# Extension_Connectors.net
KiCad netlist of a schematic drawn in Altium Designer
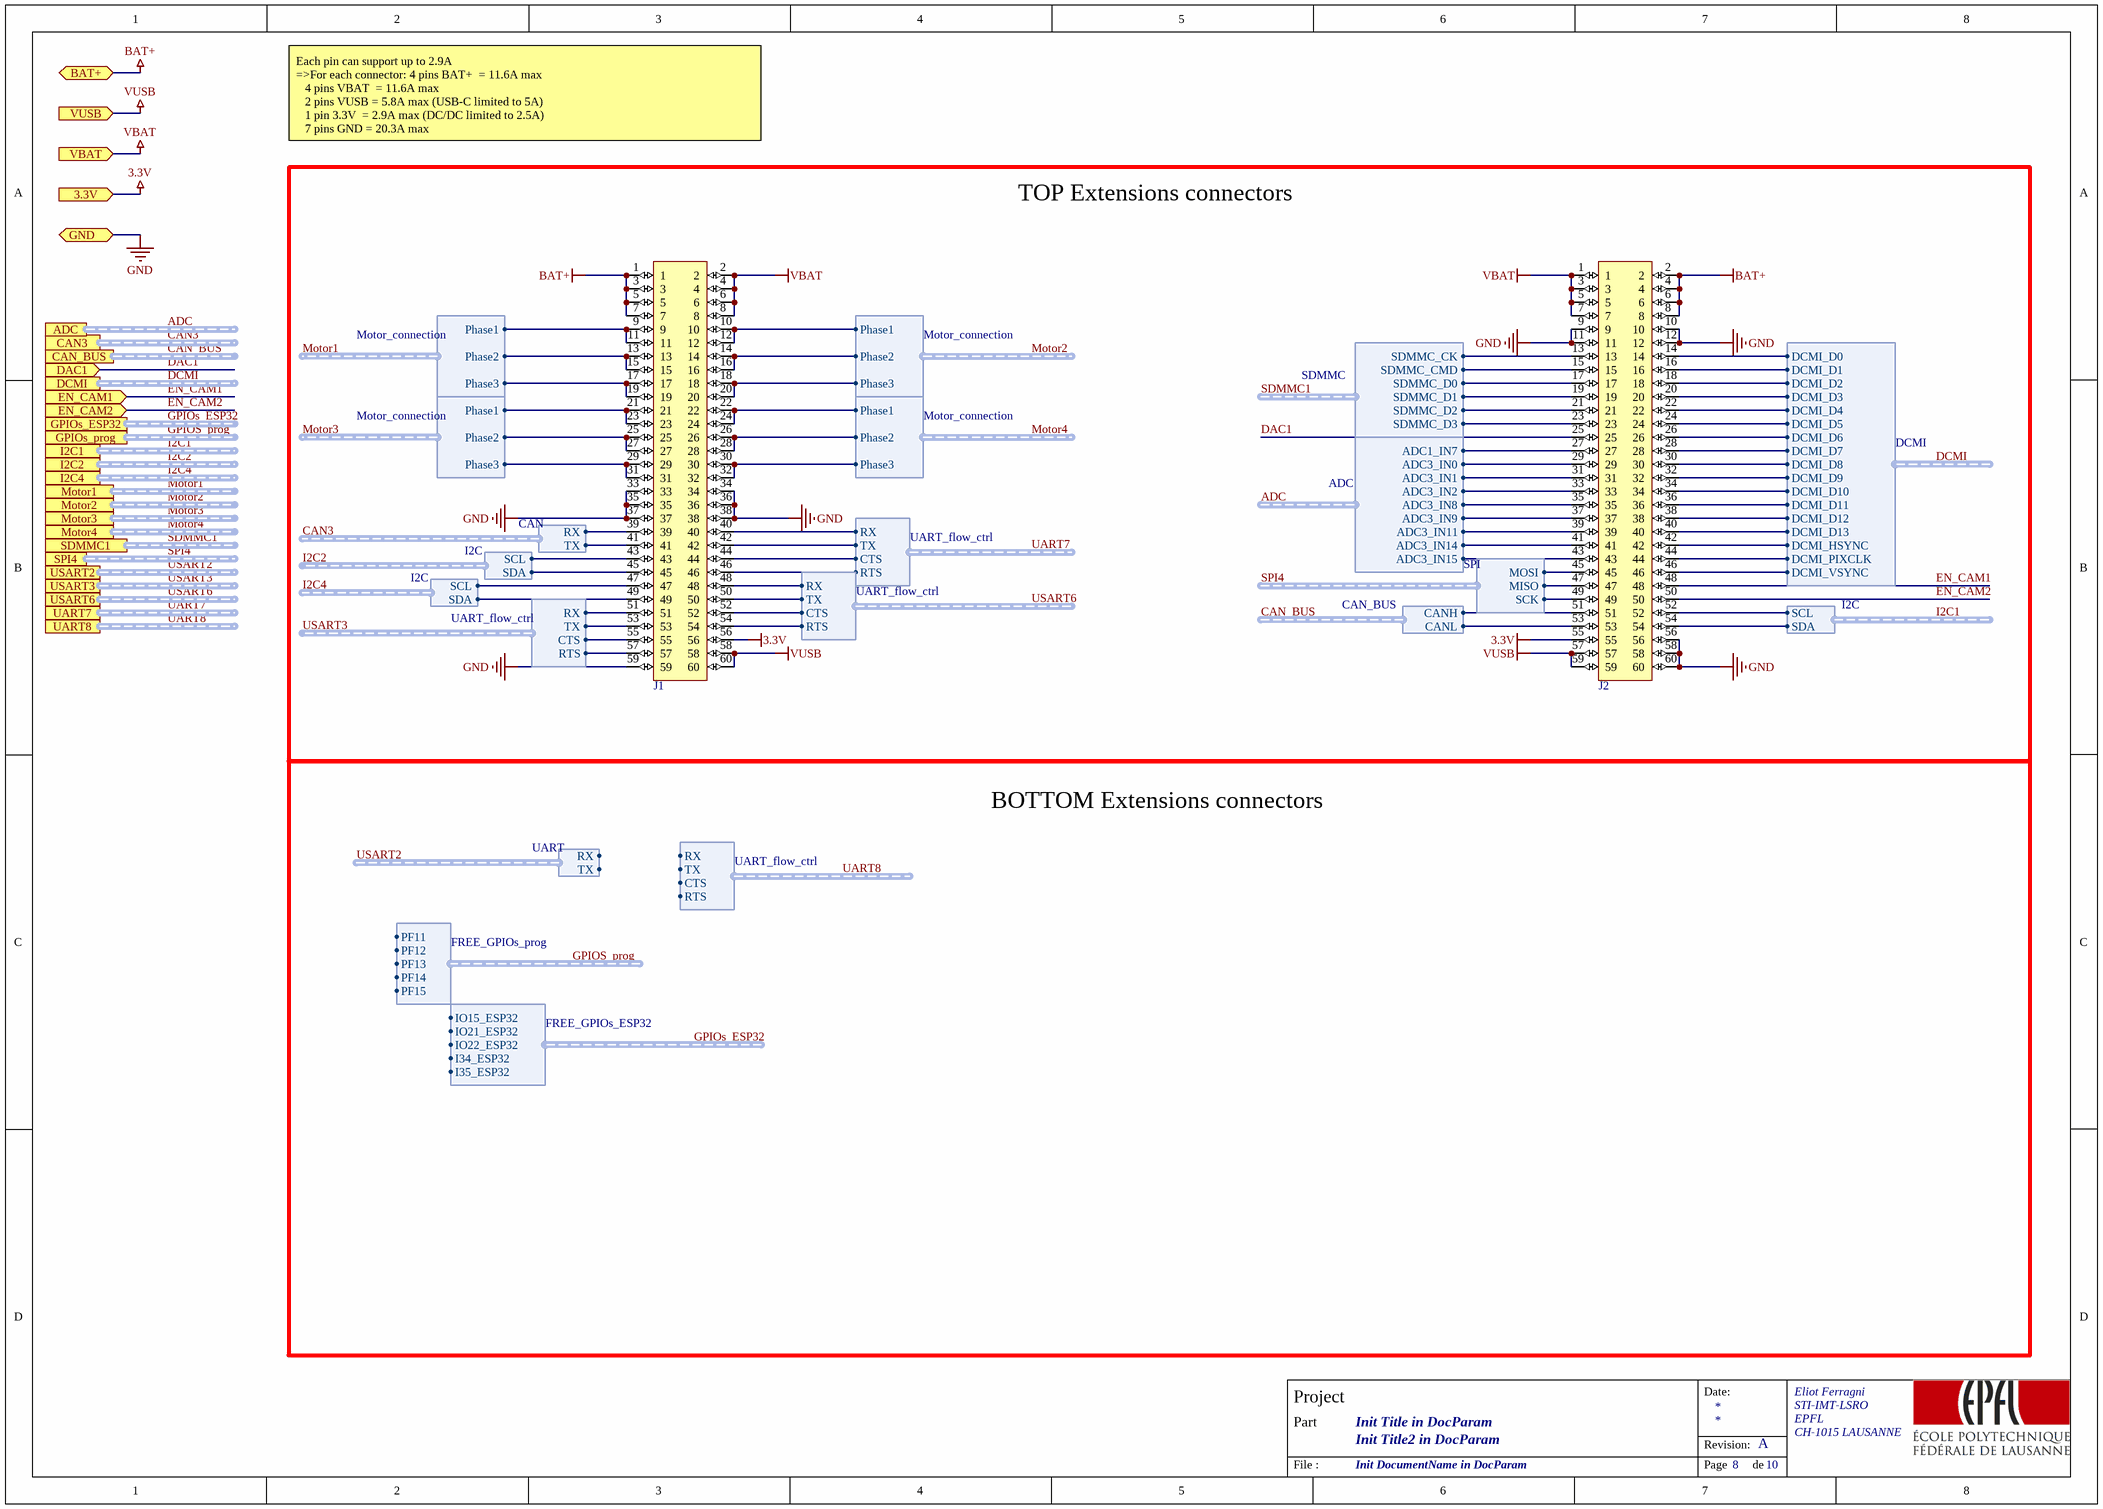
[diagram p0: Extension_Connectors.SchDoc]

(export (version "E")
  (design (tool "Eeschema 10.0.6"))
  (components
    (comp (ref "J1")
      (value "FLE-130-01-G-DV-A")
      (footprint "FLE-130-01-G-DV-A")
      (description ".050 MICRO STRIPS")
      (fields (field (name "MANUFACTURER") "Samtec Inc."))
      (libsource (lib "Schlib") (part "FLE-130-01-G-DV-A"))
    )
    (comp (ref "J2")
      (value "FLE-130-01-G-DV-A")
      (footprint "FLE-130-01-G-DV-A")
      (description ".050 MICRO STRIPS")
      (fields (field (name "MANUFACTURER") "Samtec Inc."))
      (libsource (lib "Schlib") (part "FLE-130-01-G-DV-A"))
    )
  )
  (nets
    (net (code "41") (name "/ADC1_IN7") (class "Default")
      (node (ref "J2") (pin "27") (pinfunction "27_27") (pintype "bidirectional"))
    )
    (net (code "42") (name "/ADC3_IN0") (class "Default")
      (node (ref "J2") (pin "29") (pinfunction "29_29") (pintype "bidirectional"))
    )
    (net (code "43") (name "/ADC3_IN1") (class "Default")
      (node (ref "J2") (pin "31") (pinfunction "31_31") (pintype "bidirectional"))
    )
    (net (code "44") (name "/ADC3_IN2") (class "Default")
      (node (ref "J2") (pin "33") (pinfunction "33_33") (pintype "bidirectional"))
    )
    (net (code "45") (name "/ADC3_IN8") (class "Default")
      (node (ref "J2") (pin "35") (pinfunction "35_35") (pintype "bidirectional"))
    )
    (net (code "46") (name "/ADC3_IN9") (class "Default")
      (node (ref "J2") (pin "37") (pinfunction "37_37") (pintype "bidirectional"))
    )
    (net (code "47") (name "/ADC3_IN11") (class "Default")
      (node (ref "J2") (pin "39") (pinfunction "39_39") (pintype "bidirectional"))
    )
    (net (code "48") (name "/ADC3_IN14") (class "Default")
      (node (ref "J2") (pin "41") (pinfunction "41_41") (pintype "bidirectional"))
    )
    (net (code "49") (name "/ADC3_IN15") (class "Default")
      (node (ref "J2") (pin "43") (pinfunction "43_43") (pintype "bidirectional"))
    )
    (net (code "52") (name "/CANH") (class "Default")
      (node (ref "J2") (pin "51") (pinfunction "51_51") (pintype "bidirectional"))
    )
    (net (code "53") (name "/CANL") (class "Default")
      (node (ref "J2") (pin "53") (pinfunction "53_53") (pintype "bidirectional"))
    )
    (net (code "55") (name "/DAC1") (class "Default")
      (node (ref "J2") (pin "25") (pinfunction "25_25") (pintype "bidirectional"))
    )
    (net (code "56") (name "/DCMI_D0") (class "Default")
      (node (ref "J2") (pin "14") (pinfunction "14_14") (pintype "bidirectional"))
    )
    (net (code "57") (name "/DCMI_D1") (class "Default")
      (node (ref "J2") (pin "16") (pinfunction "16_16") (pintype "bidirectional"))
    )
    (net (code "58") (name "/DCMI_D2") (class "Default")
      (node (ref "J2") (pin "18") (pinfunction "18_18") (pintype "bidirectional"))
    )
    (net (code "59") (name "/DCMI_D3") (class "Default")
      (node (ref "J2") (pin "20") (pinfunction "20_20") (pintype "bidirectional"))
    )
    (net (code "60") (name "/DCMI_D4") (class "Default")
      (node (ref "J2") (pin "22") (pinfunction "22_22") (pintype "bidirectional"))
    )
    (net (code "61") (name "/DCMI_D5") (class "Default")
      (node (ref "J2") (pin "24") (pinfunction "24_24") (pintype "bidirectional"))
    )
    (net (code "62") (name "/DCMI_D6") (class "Default")
      (node (ref "J2") (pin "26") (pinfunction "26_26") (pintype "bidirectional"))
    )
    (net (code "63") (name "/DCMI_D7") (class "Default")
      (node (ref "J2") (pin "28") (pinfunction "28_28") (pintype "bidirectional"))
    )
    (net (code "64") (name "/DCMI_D8") (class "Default")
      (node (ref "J2") (pin "30") (pinfunction "30_30") (pintype "bidirectional"))
    )
    (net (code "65") (name "/DCMI_D9") (class "Default")
      (node (ref "J2") (pin "32") (pinfunction "32_32") (pintype "bidirectional"))
    )
    (net (code "66") (name "/DCMI_D10") (class "Default")
      (node (ref "J2") (pin "34") (pinfunction "34_34") (pintype "bidirectional"))
    )
    (net (code "67") (name "/DCMI_D11") (class "Default")
      (node (ref "J2") (pin "36") (pinfunction "36_36") (pintype "bidirectional"))
    )
    (net (code "68") (name "/DCMI_D12") (class "Default")
      (node (ref "J2") (pin "38") (pinfunction "38_38") (pintype "bidirectional"))
    )
    (net (code "69") (name "/DCMI_D13") (class "Default")
      (node (ref "J2") (pin "40") (pinfunction "40_40") (pintype "bidirectional"))
    )
    (net (code "70") (name "/DCMI_HSYNC") (class "Default")
      (node (ref "J2") (pin "42") (pinfunction "42_42") (pintype "bidirectional"))
    )
    (net (code "71") (name "/DCMI_PIXCLK") (class "Default")
      (node (ref "J2") (pin "44") (pinfunction "44_44") (pintype "bidirectional"))
    )
    (net (code "72") (name "/DCMI_VSYNC") (class "Default")
      (node (ref "J2") (pin "46") (pinfunction "46_46") (pintype "bidirectional"))
    )
    (net (code "74") (name "/EN_CAM1") (class "Default")
      (node (ref "J2") (pin "48") (pinfunction "48_48") (pintype "bidirectional"))
    )
    (net (code "75") (name "/EN_CAM2") (class "Default")
      (node (ref "J2") (pin "50") (pinfunction "50_50") (pintype "bidirectional"))
    )
    (net (code "81") (name "/MISO") (class "Default")
      (node (ref "J2") (pin "47") (pinfunction "47_47") (pintype "bidirectional"))
    )
    (net (code "82") (name "/MOSI") (class "Default")
      (node (ref "J2") (pin "45") (pinfunction "45_45") (pintype "bidirectional"))
    )
    (net (code "87") (name "/SCK") (class "Default")
      (node (ref "J2") (pin "49") (pinfunction "49_49") (pintype "bidirectional"))
    )
    (net (code "89") (name "/SDMMC_CK") (class "Default")
      (node (ref "J2") (pin "13") (pinfunction "13_13") (pintype "bidirectional"))
    )
    (net (code "90") (name "/SDMMC_CMD") (class "Default")
      (node (ref "J2") (pin "15") (pinfunction "15_15") (pintype "bidirectional"))
    )
    (net (code "91") (name "/SDMMC_D0") (class "Default")
      (node (ref "J2") (pin "17") (pinfunction "17_17") (pintype "bidirectional"))
    )
    (net (code "92") (name "/SDMMC_D1") (class "Default")
      (node (ref "J2") (pin "19") (pinfunction "19_19") (pintype "bidirectional"))
    )
    (net (code "93") (name "/SDMMC_D2") (class "Default")
      (node (ref "J2") (pin "21") (pinfunction "21_21") (pintype "bidirectional"))
    )
    (net (code "94") (name "/SDMMC_D3") (class "Default")
      (node (ref "J2") (pin "23") (pinfunction "23_23") (pintype "bidirectional"))
    )
    (net (code "102") (name "3.3V") (class "Default")
      (node (ref "J1") (pin "56") (pinfunction "56_56") (pintype "bidirectional"))
      (node (ref "J2") (pin "55") (pinfunction "55_55") (pintype "bidirectional"))
    )
    (net (code "103") (name "BAT+") (class "Default")
      (node (ref "J1") (pin "1") (pinfunction "1_1") (pintype "bidirectional"))
      (node (ref "J1") (pin "3") (pinfunction "3_3") (pintype "bidirectional"))
      (node (ref "J1") (pin "5") (pinfunction "5_5") (pintype "bidirectional"))
      (node (ref "J1") (pin "7") (pinfunction "7_7") (pintype "bidirectional"))
      (node (ref "J2") (pin "2") (pinfunction "2_2") (pintype "bidirectional"))
      (node (ref "J2") (pin "4") (pinfunction "4_4") (pintype "bidirectional"))
      (node (ref "J2") (pin "6") (pinfunction "6_6") (pintype "bidirectional"))
      (node (ref "J2") (pin "8") (pinfunction "8_8") (pintype "bidirectional"))
    )
    (net (code "104") (name "GND") (class "Default")
      (node (ref "J1") (pin "33") (pinfunction "33_33") (pintype "bidirectional"))
      (node (ref "J1") (pin "34") (pinfunction "34_34") (pintype "bidirectional"))
      (node (ref "J1") (pin "35") (pinfunction "35_35") (pintype "bidirectional"))
      (node (ref "J1") (pin "36") (pinfunction "36_36") (pintype "bidirectional"))
      (node (ref "J1") (pin "37") (pinfunction "37_37") (pintype "bidirectional"))
      (node (ref "J1") (pin "38") (pinfunction "38_38") (pintype "bidirectional"))
      (node (ref "J1") (pin "59") (pinfunction "59_59") (pintype "bidirectional"))
      (node (ref "J2") (pin "10") (pinfunction "10_10") (pintype "bidirectional"))
      (node (ref "J2") (pin "11") (pinfunction "11_11") (pintype "bidirectional"))
      (node (ref "J2") (pin "12") (pinfunction "12_12") (pintype "bidirectional"))
      (node (ref "J2") (pin "56") (pinfunction "56_56") (pintype "bidirectional"))
      (node (ref "J2") (pin "58") (pinfunction "58_58") (pintype "bidirectional"))
      (node (ref "J2") (pin "60") (pinfunction "60_60") (pintype "bidirectional"))
      (node (ref "J2") (pin "9") (pinfunction "9_9") (pintype "bidirectional"))
    )
    (net (code "105") (name "Net-(J1-Pad10)") (class "Default")
      (node (ref "J1") (pin "10") (pinfunction "10_10") (pintype "bidirectional"))
      (node (ref "J1") (pin "12") (pinfunction "12_12") (pintype "bidirectional"))
    )
    (net (code "106") (name "Net-(J1-Pad11)") (class "Default")
      (node (ref "J1") (pin "11") (pinfunction "11_11") (pintype "bidirectional"))
      (node (ref "J1") (pin "9") (pinfunction "9_9") (pintype "bidirectional"))
    )
    (net (code "107") (name "Net-(J1-Pad13)") (class "Default")
      (node (ref "J1") (pin "13") (pinfunction "13_13") (pintype "bidirectional"))
      (node (ref "J1") (pin "15") (pinfunction "15_15") (pintype "bidirectional"))
    )
    (net (code "108") (name "Net-(J1-Pad14)") (class "Default")
      (node (ref "J1") (pin "14") (pinfunction "14_14") (pintype "bidirectional"))
      (node (ref "J1") (pin "16") (pinfunction "16_16") (pintype "bidirectional"))
    )
    (net (code "109") (name "Net-(J1-Pad17)") (class "Default")
      (node (ref "J1") (pin "17") (pinfunction "17_17") (pintype "bidirectional"))
      (node (ref "J1") (pin "19") (pinfunction "19_19") (pintype "bidirectional"))
    )
    (net (code "110") (name "Net-(J1-Pad18)") (class "Default")
      (node (ref "J1") (pin "18") (pinfunction "18_18") (pintype "bidirectional"))
      (node (ref "J1") (pin "20") (pinfunction "20_20") (pintype "bidirectional"))
    )
    (net (code "111") (name "Net-(J1-Pad21)") (class "Default")
      (node (ref "J1") (pin "21") (pinfunction "21_21") (pintype "bidirectional"))
      (node (ref "J1") (pin "23") (pinfunction "23_23") (pintype "bidirectional"))
    )
    (net (code "112") (name "Net-(J1-Pad22)") (class "Default")
      (node (ref "J1") (pin "22") (pinfunction "22_22") (pintype "bidirectional"))
      (node (ref "J1") (pin "24") (pinfunction "24_24") (pintype "bidirectional"))
    )
    (net (code "113") (name "Net-(J1-Pad25)") (class "Default")
      (node (ref "J1") (pin "25") (pinfunction "25_25") (pintype "bidirectional"))
      (node (ref "J1") (pin "27") (pinfunction "27_27") (pintype "bidirectional"))
    )
    (net (code "114") (name "Net-(J1-Pad26)") (class "Default")
      (node (ref "J1") (pin "26") (pinfunction "26_26") (pintype "bidirectional"))
      (node (ref "J1") (pin "28") (pinfunction "28_28") (pintype "bidirectional"))
    )
    (net (code "115") (name "Net-(J1-Pad29)") (class "Default")
      (node (ref "J1") (pin "29") (pinfunction "29_29") (pintype "bidirectional"))
      (node (ref "J1") (pin "31") (pinfunction "31_31") (pintype "bidirectional"))
    )
    (net (code "116") (name "Net-(J1-Pad30)") (class "Default")
      (node (ref "J1") (pin "30") (pinfunction "30_30") (pintype "bidirectional"))
      (node (ref "J1") (pin "32") (pinfunction "32_32") (pintype "bidirectional"))
    )
    (net (code "117") (name "VBAT") (class "Default")
      (node (ref "J1") (pin "2") (pinfunction "2_2") (pintype "bidirectional"))
      (node (ref "J1") (pin "4") (pinfunction "4_4") (pintype "bidirectional"))
      (node (ref "J1") (pin "6") (pinfunction "6_6") (pintype "bidirectional"))
      (node (ref "J1") (pin "8") (pinfunction "8_8") (pintype "bidirectional"))
      (node (ref "J2") (pin "1") (pinfunction "1_1") (pintype "bidirectional"))
      (node (ref "J2") (pin "3") (pinfunction "3_3") (pintype "bidirectional"))
      (node (ref "J2") (pin "5") (pinfunction "5_5") (pintype "bidirectional"))
      (node (ref "J2") (pin "7") (pinfunction "7_7") (pintype "bidirectional"))
    )
    (net (code "118") (name "VUSB") (class "Default")
      (node (ref "J1") (pin "58") (pinfunction "58_58") (pintype "bidirectional"))
      (node (ref "J1") (pin "60") (pinfunction "60_60") (pintype "bidirectional"))
      (node (ref "J2") (pin "57") (pinfunction "57_57") (pintype "bidirectional"))
      (node (ref "J2") (pin "59") (pinfunction "59_59") (pintype "bidirectional"))
    )
    (net (code "119") (name "unconnected-(J1-Pad39)") (class "Default")
      (node (ref "J1") (pin "39") (pinfunction "39_39") (pintype "bidirectional"))
    )
    (net (code "120") (name "unconnected-(J1-Pad40)") (class "Default")
      (node (ref "J1") (pin "40") (pinfunction "40_40") (pintype "bidirectional"))
    )
    (net (code "121") (name "unconnected-(J1-Pad41)") (class "Default")
      (node (ref "J1") (pin "41") (pinfunction "41_41") (pintype "bidirectional"))
    )
    (net (code "122") (name "unconnected-(J1-Pad42)") (class "Default")
      (node (ref "J1") (pin "42") (pinfunction "42_42") (pintype "bidirectional"))
    )
    (net (code "123") (name "unconnected-(J1-Pad43)") (class "Default")
      (node (ref "J1") (pin "43") (pinfunction "43_43") (pintype "bidirectional"))
    )
    (net (code "124") (name "unconnected-(J1-Pad44)") (class "Default")
      (node (ref "J1") (pin "44") (pinfunction "44_44") (pintype "bidirectional"))
    )
    (net (code "125") (name "unconnected-(J1-Pad45)") (class "Default")
      (node (ref "J1") (pin "45") (pinfunction "45_45") (pintype "bidirectional"))
    )
    (net (code "126") (name "unconnected-(J1-Pad46)") (class "Default")
      (node (ref "J1") (pin "46") (pinfunction "46_46") (pintype "bidirectional"))
    )
    (net (code "127") (name "unconnected-(J1-Pad47)") (class "Default")
      (node (ref "J1") (pin "47") (pinfunction "47_47") (pintype "bidirectional"))
    )
    (net (code "128") (name "unconnected-(J1-Pad48)") (class "Default")
      (node (ref "J1") (pin "48") (pinfunction "48_48") (pintype "bidirectional"))
    )
    (net (code "129") (name "unconnected-(J1-Pad49)") (class "Default")
      (node (ref "J1") (pin "49") (pinfunction "49_49") (pintype "bidirectional"))
    )
    (net (code "130") (name "unconnected-(J1-Pad50)") (class "Default")
      (node (ref "J1") (pin "50") (pinfunction "50_50") (pintype "bidirectional"))
    )
    (net (code "131") (name "unconnected-(J1-Pad51)") (class "Default")
      (node (ref "J1") (pin "51") (pinfunction "51_51") (pintype "bidirectional"))
    )
    (net (code "132") (name "unconnected-(J1-Pad52)") (class "Default")
      (node (ref "J1") (pin "52") (pinfunction "52_52") (pintype "bidirectional"))
    )
    (net (code "133") (name "unconnected-(J1-Pad53)") (class "Default")
      (node (ref "J1") (pin "53") (pinfunction "53_53") (pintype "bidirectional"))
    )
    (net (code "134") (name "unconnected-(J1-Pad54)") (class "Default")
      (node (ref "J1") (pin "54") (pinfunction "54_54") (pintype "bidirectional"))
    )
    (net (code "135") (name "unconnected-(J1-Pad55)") (class "Default")
      (node (ref "J1") (pin "55") (pinfunction "55_55") (pintype "bidirectional"))
    )
    (net (code "136") (name "unconnected-(J1-Pad57)") (class "Default")
      (node (ref "J1") (pin "57") (pinfunction "57_57") (pintype "bidirectional"))
    )
    (net (code "137") (name "unconnected-(J2-Pad52)") (class "Default")
      (node (ref "J2") (pin "52") (pinfunction "52_52") (pintype "bidirectional"))
    )
    (net (code "138") (name "unconnected-(J2-Pad54)") (class "Default")
      (node (ref "J2") (pin "54") (pinfunction "54_54") (pintype "bidirectional"))
    )
  )
)
